# Cansat2019_3279_Container_v03.net
KiCad netlist of a schematic drawn in EAGLE
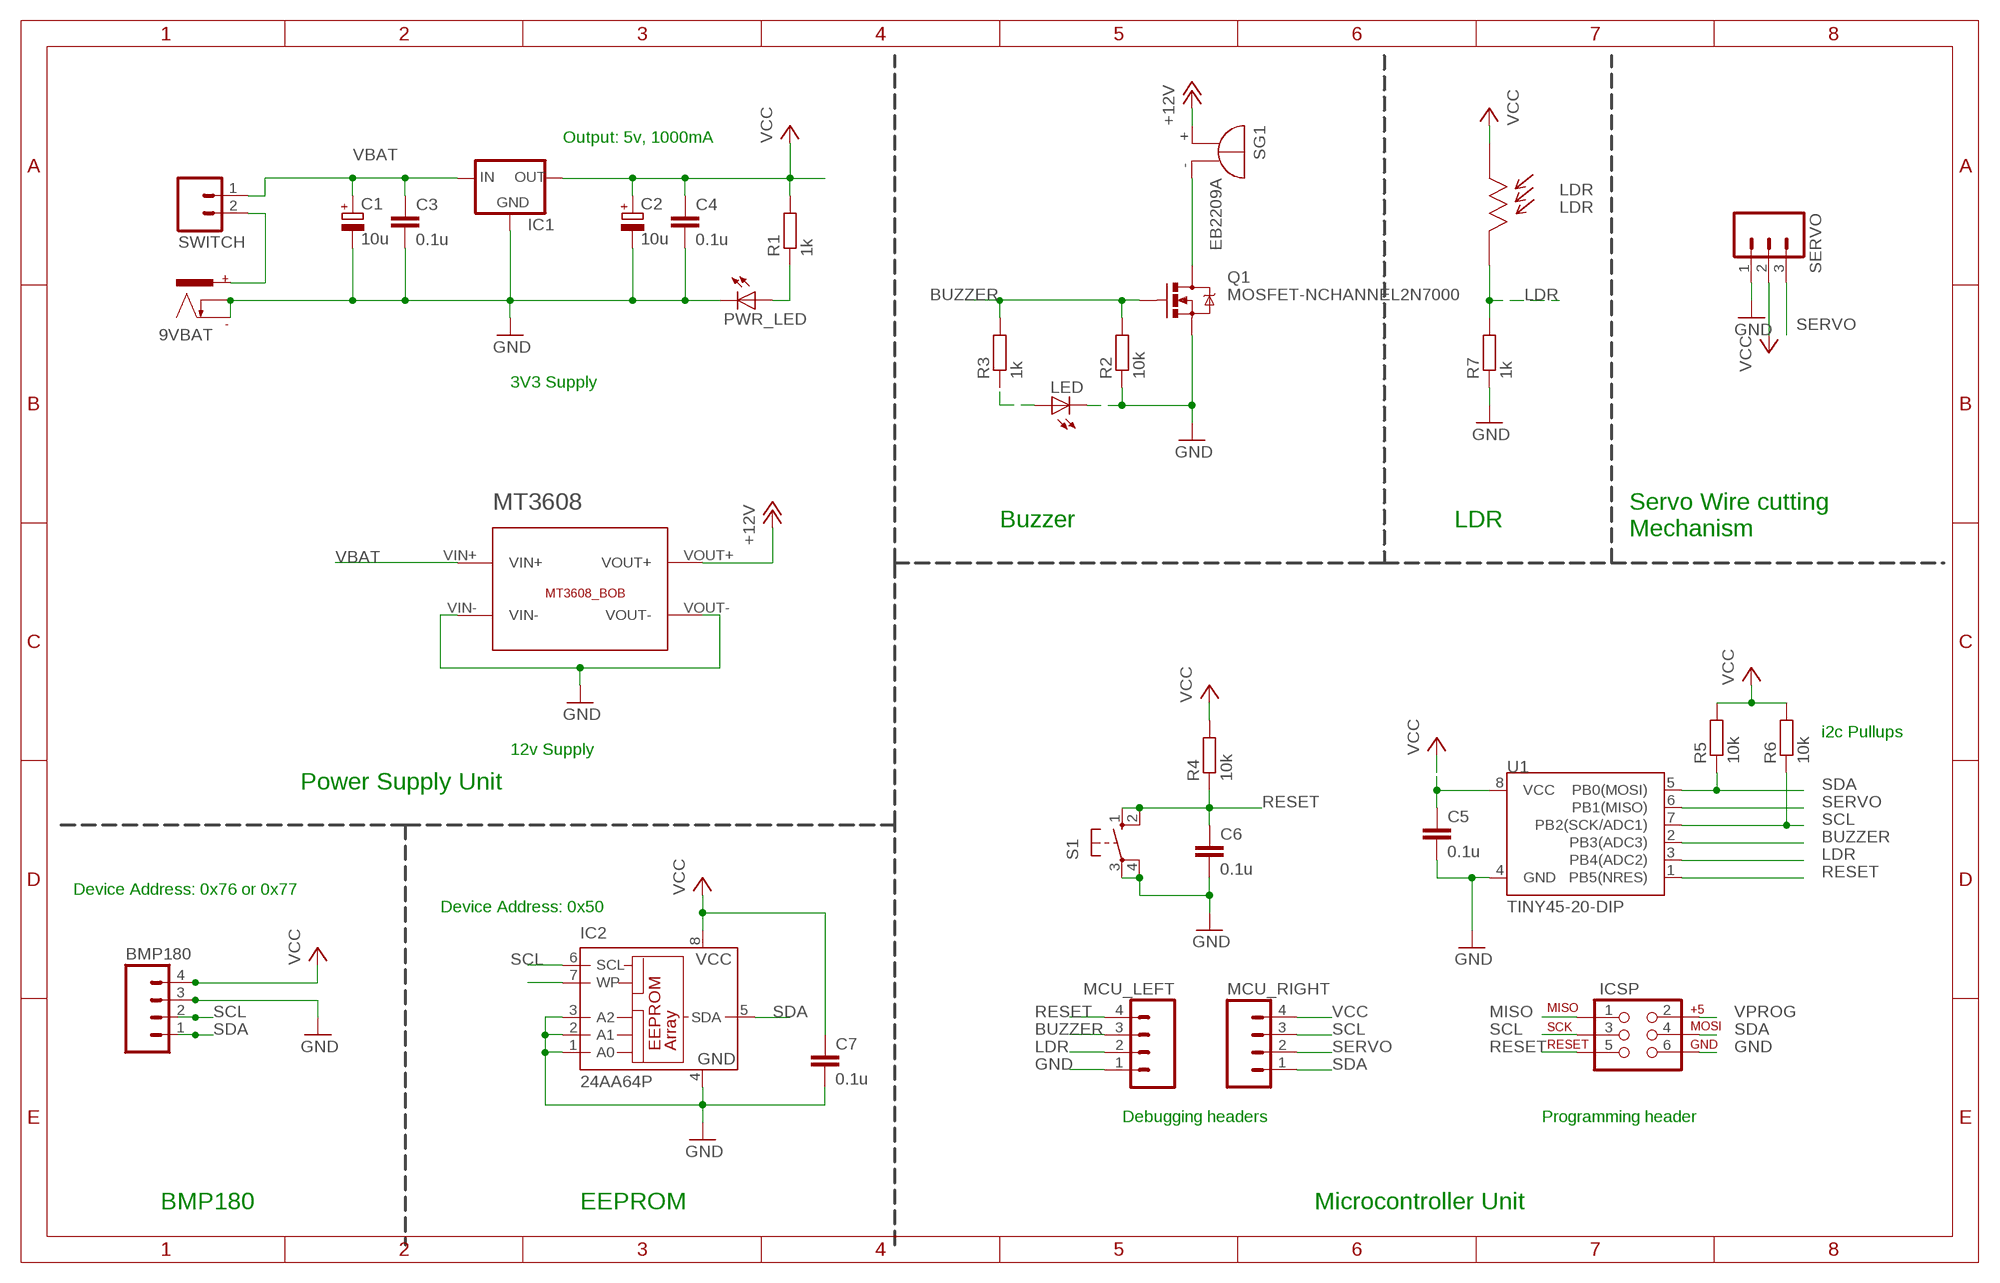
[diagram p0: schematic, sheet 1]

(export (version "E")
  (design (tool "Eeschema 10.0.6"))
  (components
    (comp (ref "9VBAT")
      (value "POWER_CON")
      (footprint "eagle-import:NEB21R")
      (libsource (lib "eagle-import") (part "POWER_CON"))
    )
    (comp (ref "BMP180")
      (value "M04")
      (footprint "eagle-import:04P")
      (libsource (lib "eagle-import") (part "M04"))
    )
    (comp (ref "C1")
      (value "10u")
      (footprint "eagle-import:E2,5-6")
      (libsource (lib "eagle-import") (part "CPOL-EUE2.5-6"))
    )
    (comp (ref "C2")
      (value "10u")
      (footprint "eagle-import:E2,5-6")
      (libsource (lib "eagle-import") (part "CPOL-EUE2.5-6"))
    )
    (comp (ref "C3")
      (value "0.1u")
      (footprint "eagle-import:C025-025X050")
      (libsource (lib "eagle-import") (part "C-EU025-025X050"))
    )
    (comp (ref "C4")
      (value "0.1u")
      (footprint "eagle-import:C025-025X050")
      (libsource (lib "eagle-import") (part "C-EU025-025X050"))
    )
    (comp (ref "C5")
      (value "0.1u")
      (footprint "eagle-import:C025-025X050")
      (libsource (lib "eagle-import") (part "C-EU025-025X050"))
    )
    (comp (ref "C6")
      (value "0.1u")
      (footprint "eagle-import:C025-025X050")
      (libsource (lib "eagle-import") (part "C-EU025-025X050"))
    )
    (comp (ref "C7")
      (value "0.1u")
      (footprint "eagle-import:C025-025X050")
      (libsource (lib "eagle-import") (part "C-EU025-025X050"))
    )
    (comp (ref "IC1")
      (value "V_REG_78XX-TO-220")
      (footprint "eagle-import:TO-220-ALT")
      (libsource (lib "eagle-import") (part "V_REG_78XX-TO-220"))
    )
    (comp (ref "IC2")
      (value "24AA64P")
      (footprint "eagle-import:DIL8")
      (fields (field (name "MF") "MICROCHIP") (field (name "MPN") "24AA64-I/P"))
      (libsource (lib "eagle-import") (part "24PAA64"))
    )
    (comp (ref "ICSP")
      (value "AVR_SPI_PRG_6NS")
      (footprint "eagle-import:2X3-NS")
      (libsource (lib "eagle-import") (part "AVR_SPI_PRG_6NS"))
    )
    (comp (ref "LDR")
      (value "LDR")
      (footprint "eagle-import:LDR-5MM")
      (libsource (lib "eagle-import") (part "LDR"))
    )
    (comp (ref "LED")
      (value "LED3MM")
      (footprint "eagle-import:LED3MM")
      (libsource (lib "eagle-import") (part "LED3MM"))
    )
    (comp (ref "MCU_LEFT")
      (value "M04")
      (footprint "eagle-import:04P")
      (libsource (lib "eagle-import") (part "M04"))
    )
    (comp (ref "MCU_RIGHT")
      (value "M04")
      (footprint "eagle-import:04P")
      (libsource (lib "eagle-import") (part "M04"))
    )
    (comp (ref "MT3608")
      (value "MT3608_BOB")
      (footprint "eagle-import:MT3608_BOB")
      (libsource (lib "eagle-import") (part "MT3608_BOB"))
    )
    (comp (ref "PWR_LED")
      (value "LED3MM")
      (footprint "eagle-import:LED3MM")
      (libsource (lib "eagle-import") (part "LED3MM"))
    )
    (comp (ref "Q1")
      (value "MOSFET-NCHANNEL2N7000")
      (footprint "eagle-import:TO-92")
      (libsource (lib "eagle-import") (part "MOSFET-NCHANNEL2N7000"))
    )
    (comp (ref "R1")
      (value "1k")
      (footprint "eagle-import:0204_7")
      (libsource (lib "eagle-import") (part "R-EU_0204/7"))
    )
    (comp (ref "R2")
      (value "10k")
      (footprint "eagle-import:0204_7")
      (libsource (lib "eagle-import") (part "R-EU_0204/7"))
    )
    (comp (ref "R3")
      (value "1k")
      (footprint "eagle-import:0204_7")
      (libsource (lib "eagle-import") (part "R-EU_0204/7"))
    )
    (comp (ref "R4")
      (value "10k")
      (footprint "eagle-import:0204_7")
      (libsource (lib "eagle-import") (part "R-EU_0204/7"))
    )
    (comp (ref "R5")
      (value "10k")
      (footprint "eagle-import:0204_7")
      (libsource (lib "eagle-import") (part "R-EU_0204/7"))
    )
    (comp (ref "R6")
      (value "10k")
      (footprint "eagle-import:0204_7")
      (libsource (lib "eagle-import") (part "R-EU_0204/7"))
    )
    (comp (ref "R7")
      (value "1k")
      (footprint "eagle-import:0204_7")
      (libsource (lib "eagle-import") (part "R-EU_0204/7"))
    )
    (comp (ref "S1")
      (value "PUSH-BUTTON-6MM")
      (footprint "eagle-import:B3F-10XX")
      (libsource (lib "eagle-import") (part "PUSH-BUTTON-6MM"))
    )
    (comp (ref "SERVO")
      (value "M03")
      (footprint "eagle-import:03P")
      (libsource (lib "eagle-import") (part "M03"))
    )
    (comp (ref "SG1")
      (value "EB2209A")
      (footprint "eagle-import:EB2209A")
      (libsource (lib "eagle-import") (part "EB2209A"))
    )
    (comp (ref "SWITCH")
      (value "M02")
      (footprint "eagle-import:02P")
      (libsource (lib "eagle-import") (part "M02"))
    )
    (comp (ref "U1")
      (value "TINY45-20-DIP")
      (footprint "eagle-import:DIP08")
      (libsource (lib "eagle-import") (part "ATTINY45TINY45-20-DIP"))
    )
  )
  (nets
    (net (code "1") (name "+12V") (class "Default")
      (node (ref "MT3608") (pin "VOUT+") (pinfunction "VOUT+_VOUT+") (pintype "bidirectional"))
      (node (ref "SG1") (pin "+") (pinfunction "+_+") (pintype "passive"))
    )
    (net (code "2") (name "/BUZZER") (class "Default")
      (node (ref "MCU_LEFT") (pin "3") (pinfunction "3_3") (pintype "passive"))
      (node (ref "Q1") (pin "2") (pinfunction "G_2") (pintype "passive"))
      (node (ref "R2") (pin "2") (pinfunction "2_2") (pintype "passive"))
      (node (ref "R3") (pin "2") (pinfunction "2_2") (pintype "passive"))
      (node (ref "U1") (pin "2") (pinfunction "PB3(ADC3)_2") (pintype "bidirectional"))
    )
    (net (code "3") (name "/LDR") (class "Default")
      (node (ref "LDR") (pin "P$2") (pinfunction "P$2_P$2") (pintype "bidirectional"))
      (node (ref "MCU_LEFT") (pin "2") (pinfunction "2_2") (pintype "passive"))
      (node (ref "R7") (pin "2") (pinfunction "2_2") (pintype "passive"))
      (node (ref "U1") (pin "3") (pinfunction "PB4(ADC2)_3") (pintype "bidirectional"))
    )
    (net (code "4") (name "/MISO") (class "Default")
      (node (ref "ICSP") (pin "1") (pinfunction "1_1") (pintype "passive"))
    )
    (net (code "5") (name "/RESET") (class "Default")
      (node (ref "C6") (pin "1") (pinfunction "1_1") (pintype "passive"))
      (node (ref "ICSP") (pin "5") (pinfunction "5_5") (pintype "passive"))
      (node (ref "MCU_LEFT") (pin "4") (pinfunction "4_4") (pintype "passive"))
      (node (ref "R4") (pin "1") (pinfunction "1_1") (pintype "passive"))
      (node (ref "S1") (pin "1") (pinfunction "S_1") (pintype "passive"))
      (node (ref "S1") (pin "2") (pinfunction "S1_2") (pintype "passive"))
      (node (ref "U1") (pin "1") (pinfunction "PB5(NRES)_1") (pintype "bidirectional"))
    )
    (net (code "6") (name "/SCL") (class "Default")
      (node (ref "BMP180") (pin "2") (pinfunction "2_2") (pintype "passive"))
      (node (ref "IC2") (pin "6") (pinfunction "SCL_6") (pintype "input"))
      (node (ref "ICSP") (pin "3") (pinfunction "3_3") (pintype "passive"))
      (node (ref "MCU_RIGHT") (pin "3") (pinfunction "3_3") (pintype "passive"))
      (node (ref "R6") (pin "1") (pinfunction "1_1") (pintype "passive"))
      (node (ref "U1") (pin "7") (pinfunction "PB2(SCK/ADC1)_7") (pintype "bidirectional"))
    )
    (net (code "7") (name "/SDA") (class "Default")
      (node (ref "BMP180") (pin "1") (pinfunction "1_1") (pintype "passive"))
      (node (ref "IC2") (pin "5") (pinfunction "SDA_5") (pintype "bidirectional"))
      (node (ref "ICSP") (pin "4") (pinfunction "4_4") (pintype "passive"))
      (node (ref "MCU_RIGHT") (pin "1") (pinfunction "1_1") (pintype "passive"))
      (node (ref "R5") (pin "1") (pinfunction "1_1") (pintype "passive"))
      (node (ref "U1") (pin "5") (pinfunction "PB0(MOSI)_5") (pintype "bidirectional"))
    )
    (net (code "8") (name "/SERVO") (class "Default")
      (node (ref "MCU_RIGHT") (pin "2") (pinfunction "2_2") (pintype "passive"))
      (node (ref "SERVO") (pin "3") (pinfunction "3_3") (pintype "passive"))
      (node (ref "U1") (pin "6") (pinfunction "PB1(MISO)_6") (pintype "bidirectional"))
    )
    (net (code "9") (name "/VBAT") (class "Default")
      (node (ref "C1") (pin "+") (pinfunction "+_+") (pintype "passive"))
      (node (ref "C3") (pin "1") (pinfunction "1_1") (pintype "passive"))
      (node (ref "IC1") (pin "IN") (pinfunction "IN_IN") (pintype "input"))
      (node (ref "MT3608") (pin "VIN+") (pinfunction "VIN+_VIN+") (pintype "bidirectional"))
      (node (ref "SWITCH") (pin "1") (pinfunction "1_1") (pintype "passive"))
    )
    (net (code "10") (name "/VPROG") (class "Default")
      (node (ref "ICSP") (pin "2") (pinfunction "2_2") (pintype "passive"))
    )
    (net (code "11") (name "GND") (class "Default")
      (node (ref "9VBAT") (pin "-") (pinfunction "-_-") (pintype "passive"))
      (node (ref "9VBAT") (pin "C") (pinfunction "C_C") (pintype "passive"))
      (node (ref "BMP180") (pin "3") (pinfunction "3_3") (pintype "passive"))
      (node (ref "C1") (pin "-") (pinfunction "-_-") (pintype "passive"))
      (node (ref "C2") (pin "-") (pinfunction "-_-") (pintype "passive"))
      (node (ref "C3") (pin "2") (pinfunction "2_2") (pintype "passive"))
      (node (ref "C4") (pin "2") (pinfunction "2_2") (pintype "passive"))
      (node (ref "C5") (pin "2") (pinfunction "2_2") (pintype "passive"))
      (node (ref "C6") (pin "2") (pinfunction "2_2") (pintype "passive"))
      (node (ref "C7") (pin "2") (pinfunction "2_2") (pintype "passive"))
      (node (ref "IC1") (pin "GND") (pinfunction "GND_GND") (pintype "input"))
      (node (ref "IC2") (pin "1") (pinfunction "A0_1") (pintype "input"))
      (node (ref "IC2") (pin "2") (pinfunction "A1_2") (pintype "input"))
      (node (ref "IC2") (pin "3") (pinfunction "A2_3") (pintype "input"))
      (node (ref "IC2") (pin "4") (pinfunction "GND_4") (pintype "power_in"))
      (node (ref "ICSP") (pin "6") (pinfunction "6_6") (pintype "passive"))
      (node (ref "LED") (pin "K") (pinfunction "C_K") (pintype "passive"))
      (node (ref "MCU_LEFT") (pin "1") (pinfunction "1_1") (pintype "passive"))
      (node (ref "MT3608") (pin "VIN-") (pinfunction "VIN-_VIN-") (pintype "bidirectional"))
      (node (ref "MT3608") (pin "VOUT-") (pinfunction "VOUT-_VOUT-") (pintype "bidirectional"))
      (node (ref "PWR_LED") (pin "K") (pinfunction "C_K") (pintype "passive"))
      (node (ref "Q1") (pin "1") (pinfunction "S_1") (pintype "passive"))
      (node (ref "R2") (pin "1") (pinfunction "1_1") (pintype "passive"))
      (node (ref "R7") (pin "1") (pinfunction "1_1") (pintype "passive"))
      (node (ref "S1") (pin "3") (pinfunction "P_3") (pintype "passive"))
      (node (ref "S1") (pin "4") (pinfunction "P1_4") (pintype "passive"))
      (node (ref "SERVO") (pin "1") (pinfunction "1_1") (pintype "passive"))
      (node (ref "U1") (pin "4") (pinfunction "GND_4") (pintype "bidirectional"))
    )
    (net (code "12") (name "Net-(9VBAT-Pad+)") (class "Default")
      (node (ref "9VBAT") (pin "+") (pinfunction "+_+") (pintype "passive"))
      (node (ref "SWITCH") (pin "2") (pinfunction "2_2") (pintype "passive"))
    )
    (net (code "13") (name "Net-(LED-PadA)") (class "Default")
      (node (ref "LED") (pin "A") (pinfunction "A_A") (pintype "passive"))
      (node (ref "R3") (pin "1") (pinfunction "1_1") (pintype "passive"))
    )
    (net (code "14") (name "Net-(PWR_LED-PadA)") (class "Default")
      (node (ref "PWR_LED") (pin "A") (pinfunction "A_A") (pintype "passive"))
      (node (ref "R1") (pin "1") (pinfunction "1_1") (pintype "passive"))
    )
    (net (code "15") (name "Net-(Q1-D)") (class "Default")
      (node (ref "Q1") (pin "3") (pinfunction "D_3") (pintype "passive"))
      (node (ref "SG1") (pin "-") (pinfunction "-_-") (pintype "passive"))
    )
    (net (code "16") (name "VCC") (class "Default")
      (node (ref "BMP180") (pin "4") (pinfunction "4_4") (pintype "passive"))
      (node (ref "C2") (pin "+") (pinfunction "+_+") (pintype "passive"))
      (node (ref "C4") (pin "1") (pinfunction "1_1") (pintype "passive"))
      (node (ref "C5") (pin "1") (pinfunction "1_1") (pintype "passive"))
      (node (ref "C7") (pin "1") (pinfunction "1_1") (pintype "passive"))
      (node (ref "IC1") (pin "OUT") (pinfunction "OUT_OUT") (pintype "output"))
      (node (ref "IC2") (pin "8") (pinfunction "VCC_8") (pintype "power_in"))
      (node (ref "LDR") (pin "P$1") (pinfunction "P$1_P$1") (pintype "bidirectional"))
      (node (ref "MCU_RIGHT") (pin "4") (pinfunction "4_4") (pintype "passive"))
      (node (ref "R1") (pin "2") (pinfunction "2_2") (pintype "passive"))
      (node (ref "R4") (pin "2") (pinfunction "2_2") (pintype "passive"))
      (node (ref "R5") (pin "2") (pinfunction "2_2") (pintype "passive"))
      (node (ref "R6") (pin "2") (pinfunction "2_2") (pintype "passive"))
      (node (ref "SERVO") (pin "2") (pinfunction "2_2") (pintype "passive"))
      (node (ref "U1") (pin "8") (pinfunction "VCC_8") (pintype "bidirectional"))
    )
    (net (code "17") (name "unconnected-(IC2-WP-Pad7)") (class "Default")
      (node (ref "IC2") (pin "7") (pinfunction "WP_7") (pintype "input"))
    )
  )
)
